# tweeq-eMod_PiezoBuzzer.net
KiCad netlist of a schematic drawn in EAGLE
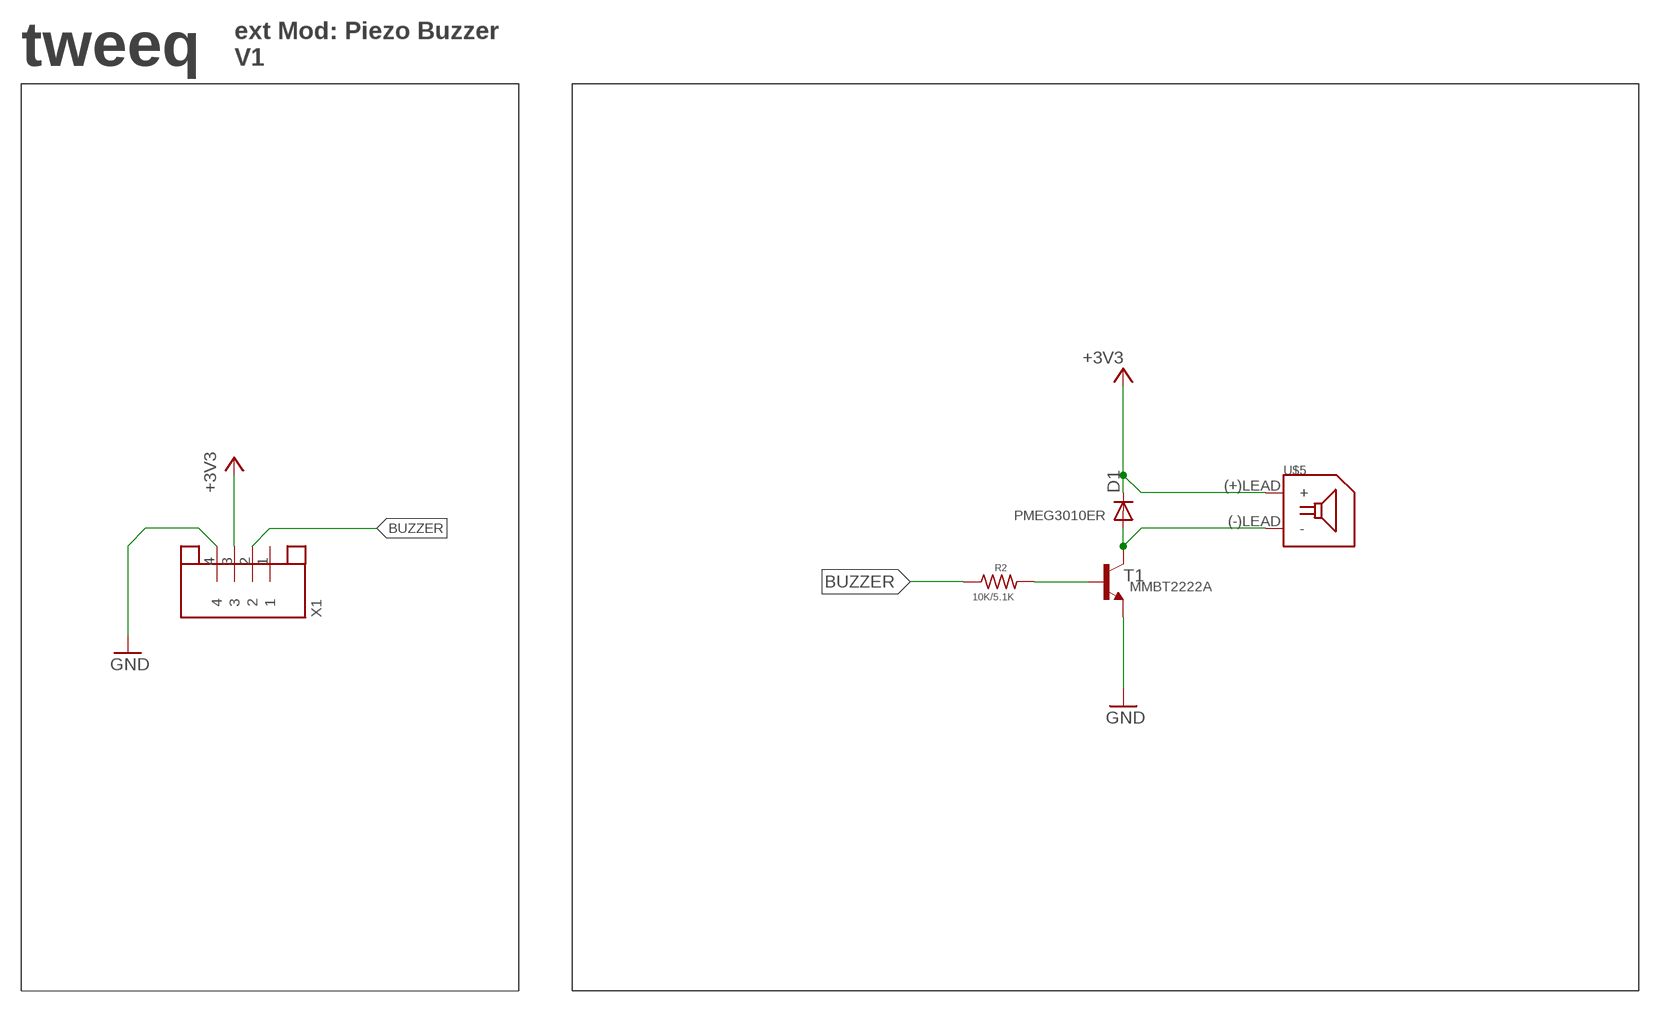
[diagram p0: schematic, sheet 1]

(export (version "E")
  (design (tool "Eeschema 10.0.6"))
  (components
    (comp (ref "D1")
      (value "PMEG3010ER")
      (footprint "eagle-import:SOD123-MOD")
      (libsource (lib "eagle-import") (part "PMEG3010ER/MOD"))
    )
    (comp (ref "R2")
      (value "10K/5.1K")
      (footprint "eagle-import:R0402")
      (libsource (lib "eagle-import") (part "R-US_R0402"))
    )
    (comp (ref "T1")
      (value "2N3904MMBT3904")
      (footprint "eagle-import:SOT23-3")
      (libsource (lib "eagle-import") (part "2N3904MMBT3904"))
    )
    (comp (ref "U$5")
      (value "SMD_PEIZO_BUZZER-DET")
      (footprint "eagle-import:DET801J-13-G")
      (libsource (lib "eagle-import") (part "SMD_PEIZO_BUZZER-DET"))
    )
    (comp (ref "X1")
      (value "JST-4PINSH")
      (footprint "eagle-import:SH1.0-4PIN")
      (libsource (lib "eagle-import") (part "JST-4PINSH"))
    )
  )
  (nets
    (net (code "1") (name "+3V3") (class "Default")
      (node (ref "D1") (pin "C") (pinfunction "C_C") (pintype "passive"))
      (node (ref "U$5") (pin "(+)LEAD") (pinfunction "+_(+)LEAD") (pintype "passive"))
      (node (ref "X1") (pin "3") (pinfunction "3_3") (pintype "bidirectional"))
    )
    (net (code "2") (name "BUZZER") (class "Default")
      (node (ref "R2") (pin "1") (pinfunction "1_1") (pintype "passive"))
      (node (ref "X1") (pin "2") (pinfunction "2_2") (pintype "bidirectional"))
    )
    (net (code "3") (name "GND") (class "Default")
      (node (ref "T1") (pin "2") (pinfunction "E_2") (pintype "passive"))
      (node (ref "X1") (pin "4") (pinfunction "4_4") (pintype "bidirectional"))
    )
    (net (code "4") (name "Net-(T1-B)") (class "Default")
      (node (ref "R2") (pin "2") (pinfunction "2_2") (pintype "passive"))
      (node (ref "T1") (pin "1") (pinfunction "B_1") (pintype "passive"))
    )
    (net (code "5") (name "Net-(T1-C)") (class "Default")
      (node (ref "D1") (pin "A") (pinfunction "A_A") (pintype "passive"))
      (node (ref "T1") (pin "3") (pinfunction "C_3") (pintype "passive"))
      (node (ref "U$5") (pin "(-)LEAD") (pinfunction "-_(-)LEAD") (pintype "passive"))
    )
    (net (code "6") (name "unconnected-(X1-Pad1)") (class "Default")
      (node (ref "X1") (pin "1") (pinfunction "1_1") (pintype "bidirectional"))
    )
  )
)
